# Coil_Board_-_Planar_Coils.net
KiCad netlist of a schematic drawn in Altium Designer
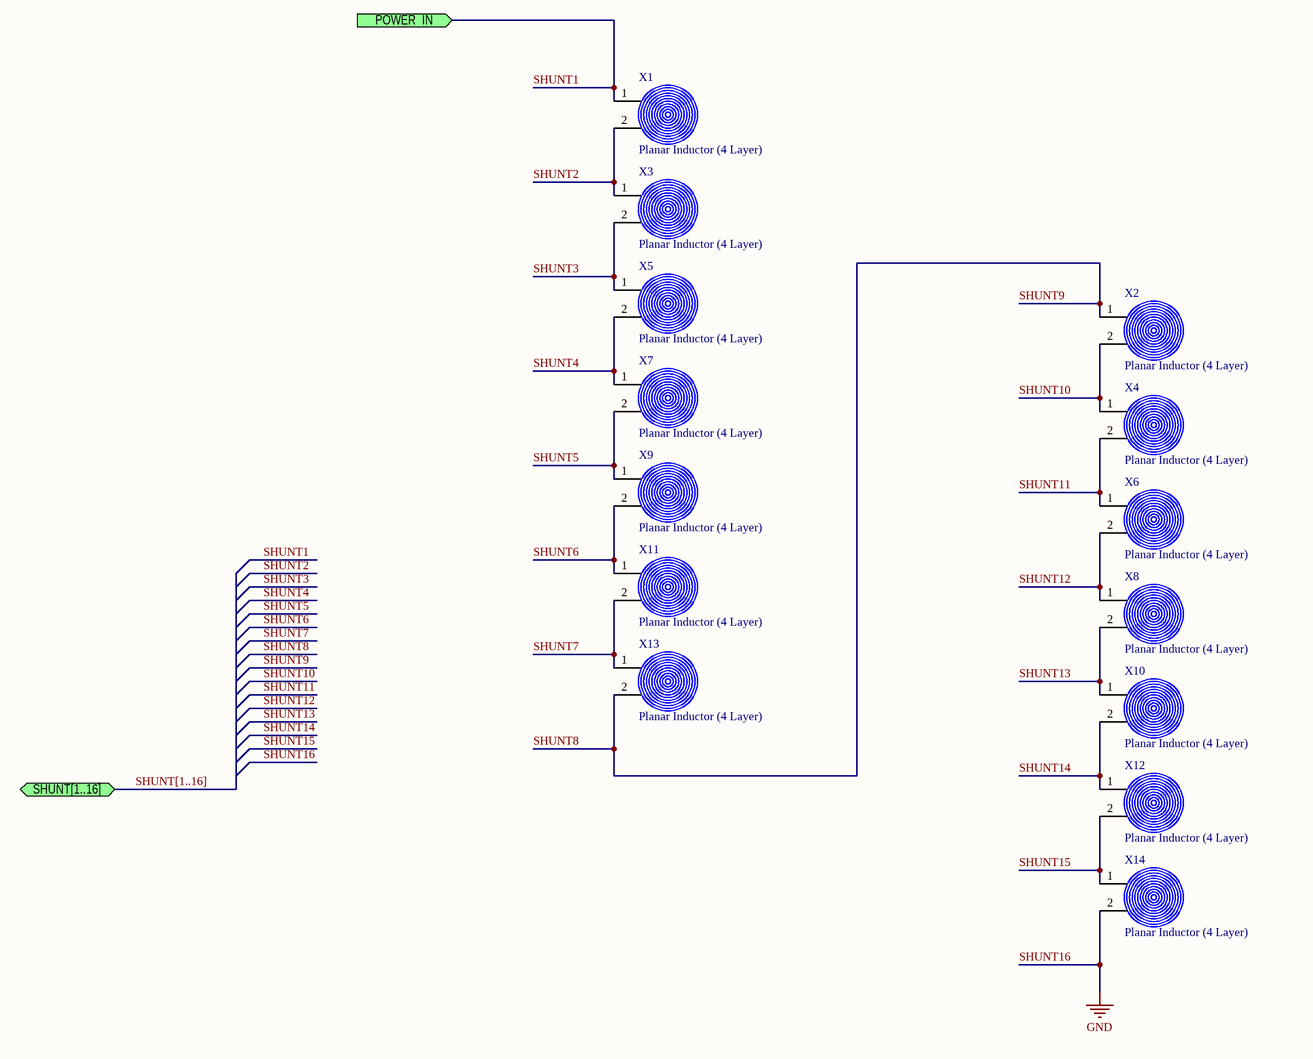
[diagram p0: Coil Board - Planar_Coils.SchDoc]

(export (version "E")
  (design (tool "Eeschema 10.0.6"))
  (components
    (comp (ref "X1")
      (value "Planar Inductor (4 Layer)")
      (footprint "Planar Coil - 44 Turns (12.5mm)")
      (libsource (lib "Altium Library") (part "Planar Coil - 44 Turns, 12mm"))
    )
    (comp (ref "X2")
      (value "Planar Inductor (4 Layer)")
      (footprint "Planar Coil - 44 Turns (12.5mm)")
      (libsource (lib "Altium Library") (part "Planar Coil - 44 Turns, 12mm"))
    )
    (comp (ref "X3")
      (value "Planar Inductor (4 Layer)")
      (footprint "Planar Coil - 44 Turns (12.5mm)")
      (libsource (lib "Altium Library") (part "Planar Coil - 44 Turns, 12mm"))
    )
    (comp (ref "X4")
      (value "Planar Inductor (4 Layer)")
      (footprint "Planar Coil - 44 Turns (12.5mm)")
      (libsource (lib "Altium Library") (part "Planar Coil - 44 Turns, 12mm"))
    )
    (comp (ref "X5")
      (value "Planar Inductor (4 Layer)")
      (footprint "Planar Coil - 44 Turns (12.5mm)")
      (libsource (lib "Altium Library") (part "Planar Coil - 44 Turns, 12mm"))
    )
    (comp (ref "X6")
      (value "Planar Inductor (4 Layer)")
      (footprint "Planar Coil - 44 Turns (12.5mm)")
      (libsource (lib "Altium Library") (part "Planar Coil - 44 Turns, 12mm"))
    )
    (comp (ref "X7")
      (value "Planar Inductor (4 Layer)")
      (footprint "Planar Coil - 44 Turns (12.5mm)")
      (libsource (lib "Altium Library") (part "Planar Coil - 44 Turns, 12mm"))
    )
    (comp (ref "X8")
      (value "Planar Inductor (4 Layer)")
      (footprint "Planar Coil - 44 Turns (12.5mm)")
      (libsource (lib "Altium Library") (part "Planar Coil - 44 Turns, 12mm"))
    )
    (comp (ref "X9")
      (value "Planar Inductor (4 Layer)")
      (footprint "Planar Coil - 44 Turns (12.5mm)")
      (libsource (lib "Altium Library") (part "Planar Coil - 44 Turns, 12mm"))
    )
    (comp (ref "X10")
      (value "Planar Inductor (4 Layer)")
      (footprint "Planar Coil - 44 Turns (12.5mm)")
      (libsource (lib "Altium Library") (part "Planar Coil - 44 Turns, 12mm"))
    )
    (comp (ref "X11")
      (value "Planar Inductor (4 Layer)")
      (footprint "Planar Coil - 44 Turns (12.5mm)")
      (libsource (lib "Altium Library") (part "Planar Coil - 44 Turns, 12mm"))
    )
    (comp (ref "X12")
      (value "Planar Inductor (4 Layer)")
      (footprint "Planar Coil - 44 Turns (12.5mm)")
      (libsource (lib "Altium Library") (part "Planar Coil - 44 Turns, 12mm"))
    )
    (comp (ref "X13")
      (value "Planar Inductor (4 Layer)")
      (footprint "Planar Coil - 44 Turns (12.5mm)")
      (libsource (lib "Altium Library") (part "Planar Coil - 44 Turns, 12mm"))
    )
    (comp (ref "X14")
      (value "Planar Inductor (4 Layer)")
      (footprint "Planar Coil - 44 Turns (12.5mm)")
      (libsource (lib "Altium Library") (part "Planar Coil - 44 Turns, 12mm"))
    )
  )
  (nets
    (net (code "1") (name "/SHUNT1") (class "Default")
      (node (ref "X1") (pin "1") (pinfunction "1_1") (pintype "passive"))
    )
    (net (code "2") (name "/SHUNT2") (class "Default")
      (node (ref "X1") (pin "2") (pinfunction "2_2") (pintype "passive"))
      (node (ref "X3") (pin "1") (pinfunction "1_1") (pintype "passive"))
    )
    (net (code "3") (name "/SHUNT3") (class "Default")
      (node (ref "X3") (pin "2") (pinfunction "2_2") (pintype "passive"))
      (node (ref "X5") (pin "1") (pinfunction "1_1") (pintype "passive"))
    )
    (net (code "4") (name "/SHUNT4") (class "Default")
      (node (ref "X5") (pin "2") (pinfunction "2_2") (pintype "passive"))
      (node (ref "X7") (pin "1") (pinfunction "1_1") (pintype "passive"))
    )
    (net (code "5") (name "/SHUNT5") (class "Default")
      (node (ref "X7") (pin "2") (pinfunction "2_2") (pintype "passive"))
      (node (ref "X9") (pin "1") (pinfunction "1_1") (pintype "passive"))
    )
    (net (code "6") (name "/SHUNT6") (class "Default")
      (node (ref "X11") (pin "1") (pinfunction "1_1") (pintype "passive"))
      (node (ref "X9") (pin "2") (pinfunction "2_2") (pintype "passive"))
    )
    (net (code "7") (name "/SHUNT7") (class "Default")
      (node (ref "X11") (pin "2") (pinfunction "2_2") (pintype "passive"))
      (node (ref "X13") (pin "1") (pinfunction "1_1") (pintype "passive"))
    )
    (net (code "8") (name "/SHUNT9") (class "Default")
      (node (ref "X13") (pin "2") (pinfunction "2_2") (pintype "passive"))
      (node (ref "X2") (pin "1") (pinfunction "1_1") (pintype "passive"))
    )
    (net (code "9") (name "/SHUNT10") (class "Default")
      (node (ref "X2") (pin "2") (pinfunction "2_2") (pintype "passive"))
      (node (ref "X4") (pin "1") (pinfunction "1_1") (pintype "passive"))
    )
    (net (code "10") (name "/SHUNT11") (class "Default")
      (node (ref "X4") (pin "2") (pinfunction "2_2") (pintype "passive"))
      (node (ref "X6") (pin "1") (pinfunction "1_1") (pintype "passive"))
    )
    (net (code "11") (name "/SHUNT12") (class "Default")
      (node (ref "X6") (pin "2") (pinfunction "2_2") (pintype "passive"))
      (node (ref "X8") (pin "1") (pinfunction "1_1") (pintype "passive"))
    )
    (net (code "12") (name "/SHUNT13") (class "Default")
      (node (ref "X10") (pin "1") (pinfunction "1_1") (pintype "passive"))
      (node (ref "X8") (pin "2") (pinfunction "2_2") (pintype "passive"))
    )
    (net (code "13") (name "/SHUNT14") (class "Default")
      (node (ref "X10") (pin "2") (pinfunction "2_2") (pintype "passive"))
      (node (ref "X12") (pin "1") (pinfunction "1_1") (pintype "passive"))
    )
    (net (code "14") (name "/SHUNT15") (class "Default")
      (node (ref "X12") (pin "2") (pinfunction "2_2") (pintype "passive"))
      (node (ref "X14") (pin "1") (pinfunction "1_1") (pintype "passive"))
    )
    (net (code "16") (name "GND") (class "Default")
      (node (ref "X14") (pin "2") (pinfunction "2_2") (pintype "passive"))
    )
  )
)
